# ftpiled.net
KiCad netlist of a schematic drawn in EAGLE
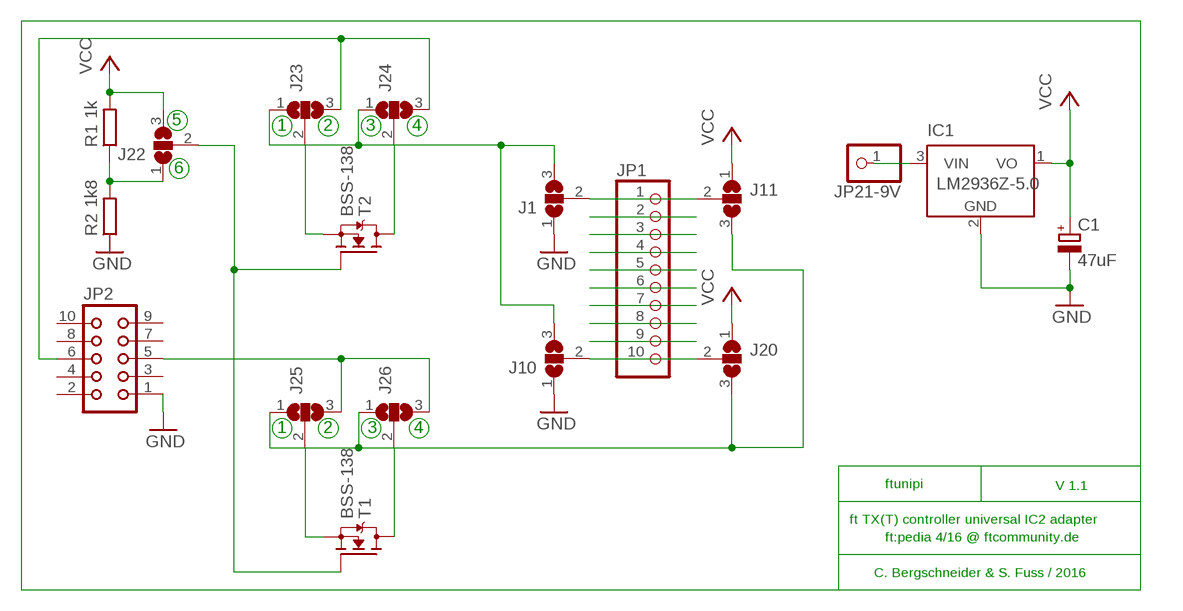
[diagram p0: schematic, sheet 1]

(export (version "E")
  (design (tool "Eeschema 10.0.6"))
  (components
    (comp (ref "C1")
      (value "47uF")
      (footprint "eagle-import:E2,5-6")
      (libsource (lib "eagle-import") (part "CPOL-EUE2.5-6"))
    )
    (comp (ref "IC1")
      (value "LM2936Z-5.0")
      (footprint "eagle-import:TO92")
      (fields (field (name "MF") "NATIONAL SEMICONDUCTOR") (field (name "MPN") "LM2936Z-5.0/NOPB"))
      (libsource (lib "eagle-import") (part "LM2936?Z-5.0"))
    )
    (comp (ref "J1")
      (value "SJ2W")
      (footprint "eagle-import:SJ_2")
      (libsource (lib "eagle-import") (part "SJ2W"))
    )
    (comp (ref "J10")
      (value "SJ2W")
      (footprint "eagle-import:SJ_2")
      (libsource (lib "eagle-import") (part "SJ2W"))
    )
    (comp (ref "J11")
      (value "SJ2W")
      (footprint "eagle-import:SJ_2")
      (libsource (lib "eagle-import") (part "SJ2W"))
    )
    (comp (ref "J20")
      (value "SJ2W")
      (footprint "eagle-import:SJ_2")
      (libsource (lib "eagle-import") (part "SJ2W"))
    )
    (comp (ref "J22")
      (value "SJ2W")
      (footprint "eagle-import:SJ_2")
      (libsource (lib "eagle-import") (part "SJ2W"))
    )
    (comp (ref "J23")
      (value "SJ2W")
      (footprint "eagle-import:SJ_2")
      (libsource (lib "eagle-import") (part "SJ2W"))
    )
    (comp (ref "J24")
      (value "SJ2W")
      (footprint "eagle-import:SJ_2")
      (libsource (lib "eagle-import") (part "SJ2W"))
    )
    (comp (ref "J25")
      (value "SJ2W")
      (footprint "eagle-import:SJ_2")
      (libsource (lib "eagle-import") (part "SJ2W"))
    )
    (comp (ref "J26")
      (value "SJ2W")
      (footprint "eagle-import:SJ_2")
      (libsource (lib "eagle-import") (part "SJ2W"))
    )
    (comp (ref "JP1")
      (value "PINHD-1X10")
      (footprint "eagle-import:1X10")
      (libsource (lib "eagle-import") (part "PINHD-1X10"))
    )
    (comp (ref "JP2")
      (value "CON10")
      (footprint "eagle-import:CON10")
      (libsource (lib "eagle-import") (part "CON10"))
    )
    (comp (ref "JP21-9V")
      (value "PINHD-1X1")
      (footprint "eagle-import:1X01")
      (libsource (lib "eagle-import") (part "PINHD-1X1"))
    )
    (comp (ref "R1")
      (value "1k")
      (footprint "eagle-import:R0805")
      (libsource (lib "eagle-import") (part "R-EU_R0805"))
    )
    (comp (ref "R2")
      (value "1k8")
      (footprint "eagle-import:R0805")
      (libsource (lib "eagle-import") (part "R-EU_R0805"))
    )
    (comp (ref "T1")
      (value "BSS-138")
      (footprint "eagle-import:SOT23")
      (libsource (lib "eagle-import") (part "MOSFET-N-SOT23"))
    )
    (comp (ref "T2")
      (value "BSS-138")
      (footprint "eagle-import:SOT23")
      (libsource (lib "eagle-import") (part "MOSFET-N-SOT23"))
    )
  )
  (nets
    (net (code "1") (name "GND") (class "Default")
      (node (ref "C1") (pin "-") (pinfunction "-_-") (pintype "passive"))
      (node (ref "IC1") (pin "2") (pinfunction "GND_2") (pintype "passive"))
      (node (ref "J1") (pin "1") (pinfunction "1_1") (pintype "passive"))
      (node (ref "J10") (pin "1") (pinfunction "1_1") (pintype "passive"))
      (node (ref "JP2") (pin "1") (pinfunction "1_1") (pintype "passive"))
      (node (ref "R2") (pin "1") (pinfunction "1_1") (pintype "passive"))
    )
    (net (code "2") (name "Net-(IC1-VIN)") (class "Default")
      (node (ref "IC1") (pin "3") (pinfunction "VIN_3") (pintype "input"))
      (node (ref "JP21-9V") (pin "1") (pinfunction "1_1") (pintype "passive"))
    )
    (net (code "3") (name "Net-(J1-Pad2)") (class "Default")
      (node (ref "J1") (pin "2") (pinfunction "2_2") (pintype "passive"))
      (node (ref "J11") (pin "2") (pinfunction "2_2") (pintype "passive"))
    )
    (net (code "4") (name "Net-(J1-Pad3)") (class "Default")
      (node (ref "J1") (pin "3") (pinfunction "3_3") (pintype "passive"))
      (node (ref "J10") (pin "3") (pinfunction "3_3") (pintype "passive"))
      (node (ref "J23") (pin "1") (pinfunction "1_1") (pintype "passive"))
      (node (ref "J24") (pin "1") (pinfunction "1_1") (pintype "passive"))
    )
    (net (code "5") (name "Net-(J10-Pad2)") (class "Default")
      (node (ref "J10") (pin "2") (pinfunction "2_2") (pintype "passive"))
      (node (ref "J20") (pin "2") (pinfunction "2_2") (pintype "passive"))
    )
    (net (code "6") (name "Net-(J11-Pad3)") (class "Default")
      (node (ref "J11") (pin "3") (pinfunction "3_3") (pintype "passive"))
      (node (ref "J20") (pin "3") (pinfunction "3_3") (pintype "passive"))
      (node (ref "J25") (pin "1") (pinfunction "1_1") (pintype "passive"))
      (node (ref "J26") (pin "1") (pinfunction "1_1") (pintype "passive"))
    )
    (net (code "7") (name "Net-(J22-Pad1)") (class "Default")
      (node (ref "J22") (pin "1") (pinfunction "1_1") (pintype "passive"))
      (node (ref "R1") (pin "1") (pinfunction "1_1") (pintype "passive"))
      (node (ref "R2") (pin "2") (pinfunction "2_2") (pintype "passive"))
    )
    (net (code "8") (name "Net-(J23-Pad3)") (class "Default")
      (node (ref "J23") (pin "3") (pinfunction "3_3") (pintype "passive"))
      (node (ref "J24") (pin "3") (pinfunction "3_3") (pintype "passive"))
      (node (ref "JP2") (pin "6") (pinfunction "6_6") (pintype "passive"))
    )
    (net (code "9") (name "Net-(J25-Pad3)") (class "Default")
      (node (ref "J25") (pin "3") (pinfunction "3_3") (pintype "passive"))
      (node (ref "J26") (pin "3") (pinfunction "3_3") (pintype "passive"))
      (node (ref "JP2") (pin "5") (pinfunction "5_5") (pintype "passive"))
    )
    (net (code "10") (name "Net-(T1-D)") (class "Default")
      (node (ref "J26") (pin "2") (pinfunction "2_2") (pintype "passive"))
      (node (ref "T1") (pin "3") (pinfunction "D_3") (pintype "passive"))
    )
    (net (code "11") (name "Net-(T1-G)") (class "Default")
      (node (ref "J22") (pin "2") (pinfunction "2_2") (pintype "passive"))
      (node (ref "T1") (pin "1") (pinfunction "G_1") (pintype "passive"))
      (node (ref "T2") (pin "1") (pinfunction "G_1") (pintype "passive"))
    )
    (net (code "12") (name "Net-(T1-S)") (class "Default")
      (node (ref "J25") (pin "2") (pinfunction "2_2") (pintype "passive"))
      (node (ref "T1") (pin "2") (pinfunction "S_2") (pintype "passive"))
    )
    (net (code "13") (name "Net-(T2-D)") (class "Default")
      (node (ref "J24") (pin "2") (pinfunction "2_2") (pintype "passive"))
      (node (ref "T2") (pin "3") (pinfunction "D_3") (pintype "passive"))
    )
    (net (code "14") (name "Net-(T2-S)") (class "Default")
      (node (ref "J23") (pin "2") (pinfunction "2_2") (pintype "passive"))
      (node (ref "T2") (pin "2") (pinfunction "S_2") (pintype "passive"))
    )
    (net (code "15") (name "VCC") (class "Default")
      (node (ref "C1") (pin "+") (pinfunction "+_+") (pintype "passive"))
      (node (ref "IC1") (pin "1") (pinfunction "VO_1") (pintype "passive"))
      (node (ref "J11") (pin "1") (pinfunction "1_1") (pintype "passive"))
      (node (ref "J20") (pin "1") (pinfunction "1_1") (pintype "passive"))
      (node (ref "J22") (pin "3") (pinfunction "3_3") (pintype "passive"))
      (node (ref "R1") (pin "2") (pinfunction "2_2") (pintype "passive"))
    )
    (net (code "16") (name "unconnected-(JP1-Pad1)") (class "Default")
      (node (ref "JP1") (pin "1") (pinfunction "1_1") (pintype "passive"))
    )
    (net (code "17") (name "unconnected-(JP1-Pad2)") (class "Default")
      (node (ref "JP1") (pin "2") (pinfunction "2_2") (pintype "passive"))
    )
    (net (code "18") (name "unconnected-(JP1-Pad3)") (class "Default")
      (node (ref "JP1") (pin "3") (pinfunction "3_3") (pintype "passive"))
    )
    (net (code "19") (name "unconnected-(JP1-Pad4)") (class "Default")
      (node (ref "JP1") (pin "4") (pinfunction "4_4") (pintype "passive"))
    )
    (net (code "20") (name "unconnected-(JP1-Pad5)") (class "Default")
      (node (ref "JP1") (pin "5") (pinfunction "5_5") (pintype "passive"))
    )
    (net (code "21") (name "unconnected-(JP1-Pad6)") (class "Default")
      (node (ref "JP1") (pin "6") (pinfunction "6_6") (pintype "passive"))
    )
    (net (code "22") (name "unconnected-(JP1-Pad7)") (class "Default")
      (node (ref "JP1") (pin "7") (pinfunction "7_7") (pintype "passive"))
    )
    (net (code "23") (name "unconnected-(JP1-Pad8)") (class "Default")
      (node (ref "JP1") (pin "8") (pinfunction "8_8") (pintype "passive"))
    )
    (net (code "24") (name "unconnected-(JP1-Pad9)") (class "Default")
      (node (ref "JP1") (pin "9") (pinfunction "9_9") (pintype "passive"))
    )
    (net (code "25") (name "unconnected-(JP1-Pad10)") (class "Default")
      (node (ref "JP1") (pin "10") (pinfunction "10_10") (pintype "passive"))
    )
    (net (code "26") (name "unconnected-(JP2-Pad2)") (class "Default")
      (node (ref "JP2") (pin "2") (pinfunction "2_2") (pintype "passive"))
    )
    (net (code "27") (name "unconnected-(JP2-Pad3)") (class "Default")
      (node (ref "JP2") (pin "3") (pinfunction "3_3") (pintype "passive"))
    )
    (net (code "28") (name "unconnected-(JP2-Pad4)") (class "Default")
      (node (ref "JP2") (pin "4") (pinfunction "4_4") (pintype "passive"))
    )
    (net (code "29") (name "unconnected-(JP2-Pad7)") (class "Default")
      (node (ref "JP2") (pin "7") (pinfunction "7_7") (pintype "passive"))
    )
    (net (code "30") (name "unconnected-(JP2-Pad8)") (class "Default")
      (node (ref "JP2") (pin "8") (pinfunction "8_8") (pintype "passive"))
    )
    (net (code "31") (name "unconnected-(JP2-Pad9)") (class "Default")
      (node (ref "JP2") (pin "9") (pinfunction "9_9") (pintype "passive"))
    )
    (net (code "32") (name "unconnected-(JP2-Pad10)") (class "Default")
      (node (ref "JP2") (pin "10") (pinfunction "10_10") (pintype "passive"))
    )
  )
)
